# dcy_vca_v1_0_1_pnl.net
KiCad netlist of a schematic drawn in EAGLE
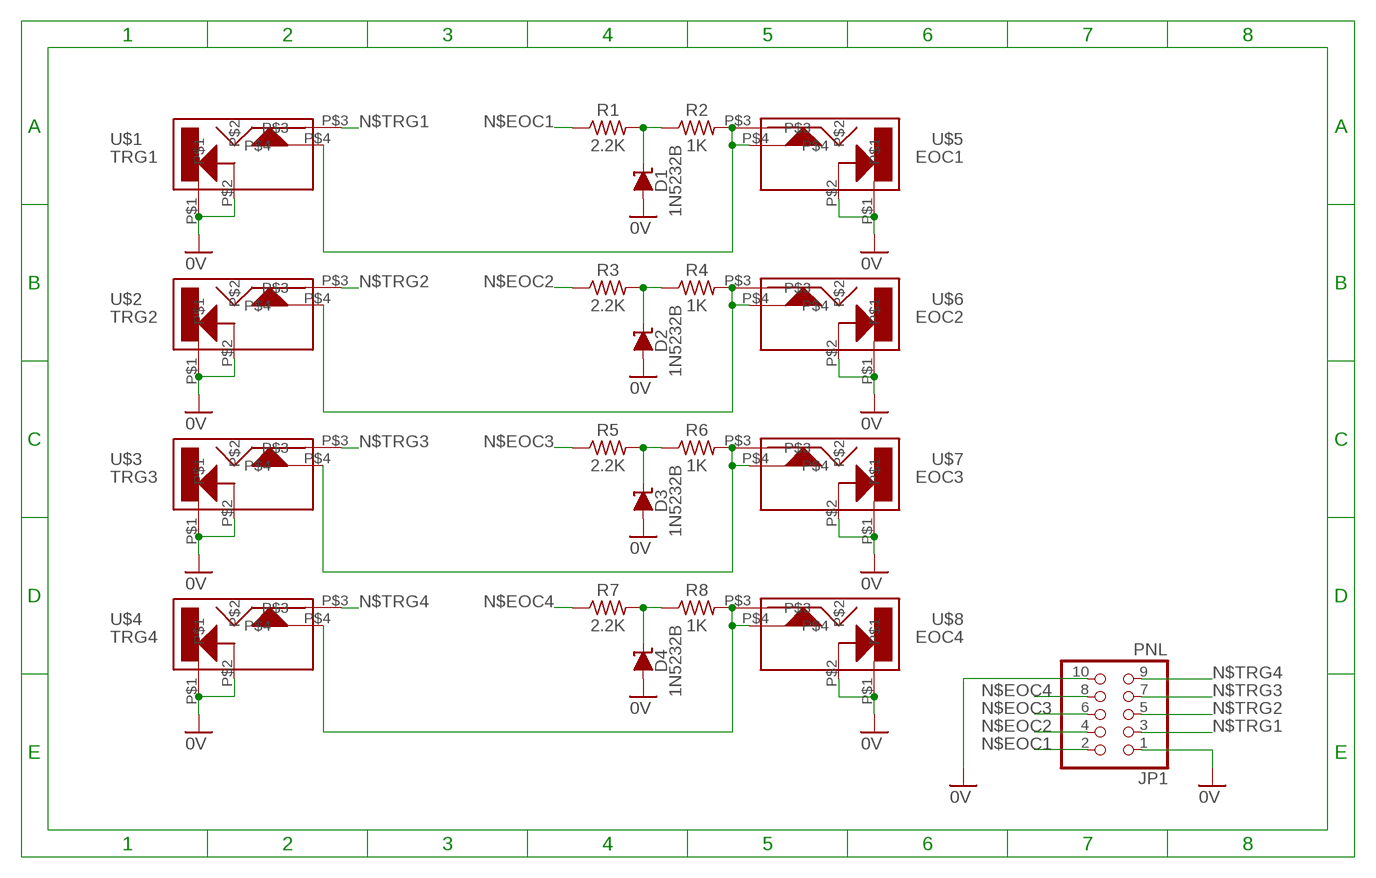
[diagram p0: schematic, sheet 1]

(export (version "E")
  (design (tool "Eeschema 10.0.6"))
  (components
    (comp (ref "D1")
      (value "1N5232B")
      (footprint "eagle-import:DO34-5")
      (libsource (lib "eagle-import") (part "1N5232B"))
    )
    (comp (ref "D2")
      (value "1N5232B")
      (footprint "eagle-import:DO34-5")
      (libsource (lib "eagle-import") (part "1N5232B"))
    )
    (comp (ref "D3")
      (value "1N5232B")
      (footprint "eagle-import:DO34-5")
      (libsource (lib "eagle-import") (part "1N5232B"))
    )
    (comp (ref "D4")
      (value "1N5232B")
      (footprint "eagle-import:DO34-5")
      (libsource (lib "eagle-import") (part "1N5232B"))
    )
    (comp (ref "JP1")
      (value "PNL")
      (footprint "eagle-import:2X05")
      (libsource (lib "eagle-import") (part "PINHD-2X5"))
    )
    (comp (ref "R1")
      (value "2.2K")
      (footprint "eagle-import:0207_7")
      (libsource (lib "eagle-import") (part "R"))
    )
    (comp (ref "R2")
      (value "1K")
      (footprint "eagle-import:0207_7")
      (libsource (lib "eagle-import") (part "R"))
    )
    (comp (ref "R3")
      (value "2.2K")
      (footprint "eagle-import:0207_7")
      (libsource (lib "eagle-import") (part "R"))
    )
    (comp (ref "R4")
      (value "1K")
      (footprint "eagle-import:0207_7")
      (libsource (lib "eagle-import") (part "R"))
    )
    (comp (ref "R5")
      (value "2.2K")
      (footprint "eagle-import:0207_7")
      (libsource (lib "eagle-import") (part "R"))
    )
    (comp (ref "R6")
      (value "1K")
      (footprint "eagle-import:0207_7")
      (libsource (lib "eagle-import") (part "R"))
    )
    (comp (ref "R7")
      (value "2.2K")
      (footprint "eagle-import:0207_7")
      (libsource (lib "eagle-import") (part "R"))
    )
    (comp (ref "R8")
      (value "1K")
      (footprint "eagle-import:0207_7")
      (libsource (lib "eagle-import") (part "R"))
    )
    (comp (ref "U$1")
      (value "TRG1")
      (footprint "eagle-import:CL1384")
      (libsource (lib "eagle-import") (part "CL1384"))
    )
    (comp (ref "U$2")
      (value "TRG2")
      (footprint "eagle-import:CL1384")
      (libsource (lib "eagle-import") (part "CL1384"))
    )
    (comp (ref "U$3")
      (value "TRG3")
      (footprint "eagle-import:CL1384")
      (libsource (lib "eagle-import") (part "CL1384"))
    )
    (comp (ref "U$4")
      (value "TRG4")
      (footprint "eagle-import:CL1384")
      (libsource (lib "eagle-import") (part "CL1384"))
    )
    (comp (ref "U$5")
      (value "EOC1")
      (footprint "eagle-import:CL1384")
      (libsource (lib "eagle-import") (part "CL1384"))
    )
    (comp (ref "U$6")
      (value "EOC2")
      (footprint "eagle-import:CL1384")
      (libsource (lib "eagle-import") (part "CL1384"))
    )
    (comp (ref "U$7")
      (value "EOC3")
      (footprint "eagle-import:CL1384")
      (libsource (lib "eagle-import") (part "CL1384"))
    )
    (comp (ref "U$8")
      (value "EOC4")
      (footprint "eagle-import:CL1384")
      (libsource (lib "eagle-import") (part "CL1384"))
    )
  )
  (nets
    (net (code "1") (name "/N$EOC1") (class "Default")
      (node (ref "JP1") (pin "2") (pinfunction "2_2") (pintype "passive"))
      (node (ref "R1") (pin "1") (pinfunction "1_1") (pintype "passive"))
    )
    (net (code "2") (name "/N$EOC2") (class "Default")
      (node (ref "JP1") (pin "4") (pinfunction "4_4") (pintype "passive"))
      (node (ref "R3") (pin "1") (pinfunction "1_1") (pintype "passive"))
    )
    (net (code "3") (name "/N$EOC3") (class "Default")
      (node (ref "JP1") (pin "6") (pinfunction "6_6") (pintype "passive"))
      (node (ref "R5") (pin "1") (pinfunction "1_1") (pintype "passive"))
    )
    (net (code "4") (name "/N$EOC4") (class "Default")
      (node (ref "JP1") (pin "8") (pinfunction "8_8") (pintype "passive"))
      (node (ref "R7") (pin "1") (pinfunction "1_1") (pintype "passive"))
    )
    (net (code "5") (name "/N$TRG1") (class "Default")
      (node (ref "JP1") (pin "3") (pinfunction "3_3") (pintype "passive"))
      (node (ref "U$1") (pin "P$3") (pinfunction "P$3_P$3") (pintype "bidirectional"))
    )
    (net (code "6") (name "/N$TRG2") (class "Default")
      (node (ref "JP1") (pin "5") (pinfunction "5_5") (pintype "passive"))
      (node (ref "U$2") (pin "P$3") (pinfunction "P$3_P$3") (pintype "bidirectional"))
    )
    (net (code "7") (name "/N$TRG3") (class "Default")
      (node (ref "JP1") (pin "7") (pinfunction "7_7") (pintype "passive"))
      (node (ref "U$3") (pin "P$3") (pinfunction "P$3_P$3") (pintype "bidirectional"))
    )
    (net (code "8") (name "/N$TRG4") (class "Default")
      (node (ref "JP1") (pin "9") (pinfunction "9_9") (pintype "passive"))
      (node (ref "U$4") (pin "P$3") (pinfunction "P$3_P$3") (pintype "bidirectional"))
    )
    (net (code "9") (name "0V") (class "Default")
      (node (ref "D1") (pin "A") (pinfunction "A_A") (pintype "passive"))
      (node (ref "D2") (pin "A") (pinfunction "A_A") (pintype "passive"))
      (node (ref "D3") (pin "A") (pinfunction "A_A") (pintype "passive"))
      (node (ref "D4") (pin "A") (pinfunction "A_A") (pintype "passive"))
      (node (ref "JP1") (pin "1") (pinfunction "1_1") (pintype "passive"))
      (node (ref "JP1") (pin "10") (pinfunction "10_10") (pintype "passive"))
      (node (ref "U$1") (pin "P$1") (pinfunction "P$1_P$1") (pintype "bidirectional"))
      (node (ref "U$1") (pin "P$2") (pinfunction "P$2_P$2") (pintype "bidirectional"))
      (node (ref "U$2") (pin "P$1") (pinfunction "P$1_P$1") (pintype "bidirectional"))
      (node (ref "U$2") (pin "P$2") (pinfunction "P$2_P$2") (pintype "bidirectional"))
      (node (ref "U$3") (pin "P$1") (pinfunction "P$1_P$1") (pintype "bidirectional"))
      (node (ref "U$3") (pin "P$2") (pinfunction "P$2_P$2") (pintype "bidirectional"))
      (node (ref "U$4") (pin "P$1") (pinfunction "P$1_P$1") (pintype "bidirectional"))
      (node (ref "U$4") (pin "P$2") (pinfunction "P$2_P$2") (pintype "bidirectional"))
      (node (ref "U$5") (pin "P$1") (pinfunction "P$1_P$1") (pintype "bidirectional"))
      (node (ref "U$5") (pin "P$2") (pinfunction "P$2_P$2") (pintype "bidirectional"))
      (node (ref "U$6") (pin "P$1") (pinfunction "P$1_P$1") (pintype "bidirectional"))
      (node (ref "U$6") (pin "P$2") (pinfunction "P$2_P$2") (pintype "bidirectional"))
      (node (ref "U$7") (pin "P$1") (pinfunction "P$1_P$1") (pintype "bidirectional"))
      (node (ref "U$7") (pin "P$2") (pinfunction "P$2_P$2") (pintype "bidirectional"))
      (node (ref "U$8") (pin "P$1") (pinfunction "P$1_P$1") (pintype "bidirectional"))
      (node (ref "U$8") (pin "P$2") (pinfunction "P$2_P$2") (pintype "bidirectional"))
    )
    (net (code "10") (name "Net-(D1-PadC)") (class "Default")
      (node (ref "D1") (pin "C") (pinfunction "C_C") (pintype "passive"))
      (node (ref "R1") (pin "2") (pinfunction "2_2") (pintype "passive"))
      (node (ref "R2") (pin "1") (pinfunction "1_1") (pintype "passive"))
    )
    (net (code "11") (name "Net-(D2-PadC)") (class "Default")
      (node (ref "D2") (pin "C") (pinfunction "C_C") (pintype "passive"))
      (node (ref "R3") (pin "2") (pinfunction "2_2") (pintype "passive"))
      (node (ref "R4") (pin "1") (pinfunction "1_1") (pintype "passive"))
    )
    (net (code "12") (name "Net-(D3-PadC)") (class "Default")
      (node (ref "D3") (pin "C") (pinfunction "C_C") (pintype "passive"))
      (node (ref "R5") (pin "2") (pinfunction "2_2") (pintype "passive"))
      (node (ref "R6") (pin "1") (pinfunction "1_1") (pintype "passive"))
    )
    (net (code "13") (name "Net-(D4-PadC)") (class "Default")
      (node (ref "D4") (pin "C") (pinfunction "C_C") (pintype "passive"))
      (node (ref "R7") (pin "2") (pinfunction "2_2") (pintype "passive"))
      (node (ref "R8") (pin "1") (pinfunction "1_1") (pintype "passive"))
    )
    (net (code "14") (name "Net-(R2-Pad2)") (class "Default")
      (node (ref "R2") (pin "2") (pinfunction "2_2") (pintype "passive"))
      (node (ref "U$1") (pin "P$4") (pinfunction "P$4_P$4") (pintype "bidirectional"))
      (node (ref "U$5") (pin "P$3") (pinfunction "P$3_P$3") (pintype "bidirectional"))
      (node (ref "U$5") (pin "P$4") (pinfunction "P$4_P$4") (pintype "bidirectional"))
    )
    (net (code "15") (name "Net-(R4-Pad2)") (class "Default")
      (node (ref "R4") (pin "2") (pinfunction "2_2") (pintype "passive"))
      (node (ref "U$2") (pin "P$4") (pinfunction "P$4_P$4") (pintype "bidirectional"))
      (node (ref "U$6") (pin "P$3") (pinfunction "P$3_P$3") (pintype "bidirectional"))
      (node (ref "U$6") (pin "P$4") (pinfunction "P$4_P$4") (pintype "bidirectional"))
    )
    (net (code "16") (name "Net-(R6-Pad2)") (class "Default")
      (node (ref "R6") (pin "2") (pinfunction "2_2") (pintype "passive"))
      (node (ref "U$3") (pin "P$4") (pinfunction "P$4_P$4") (pintype "bidirectional"))
      (node (ref "U$7") (pin "P$3") (pinfunction "P$3_P$3") (pintype "bidirectional"))
      (node (ref "U$7") (pin "P$4") (pinfunction "P$4_P$4") (pintype "bidirectional"))
    )
    (net (code "17") (name "Net-(R8-Pad2)") (class "Default")
      (node (ref "R8") (pin "2") (pinfunction "2_2") (pintype "passive"))
      (node (ref "U$4") (pin "P$4") (pinfunction "P$4_P$4") (pintype "bidirectional"))
      (node (ref "U$8") (pin "P$3") (pinfunction "P$3_P$3") (pintype "bidirectional"))
      (node (ref "U$8") (pin "P$4") (pinfunction "P$4_P$4") (pintype "bidirectional"))
    )
  )
)
